# PiOBD_CM4_USB3.net
KiCad netlist of a schematic drawn in Altium Designer
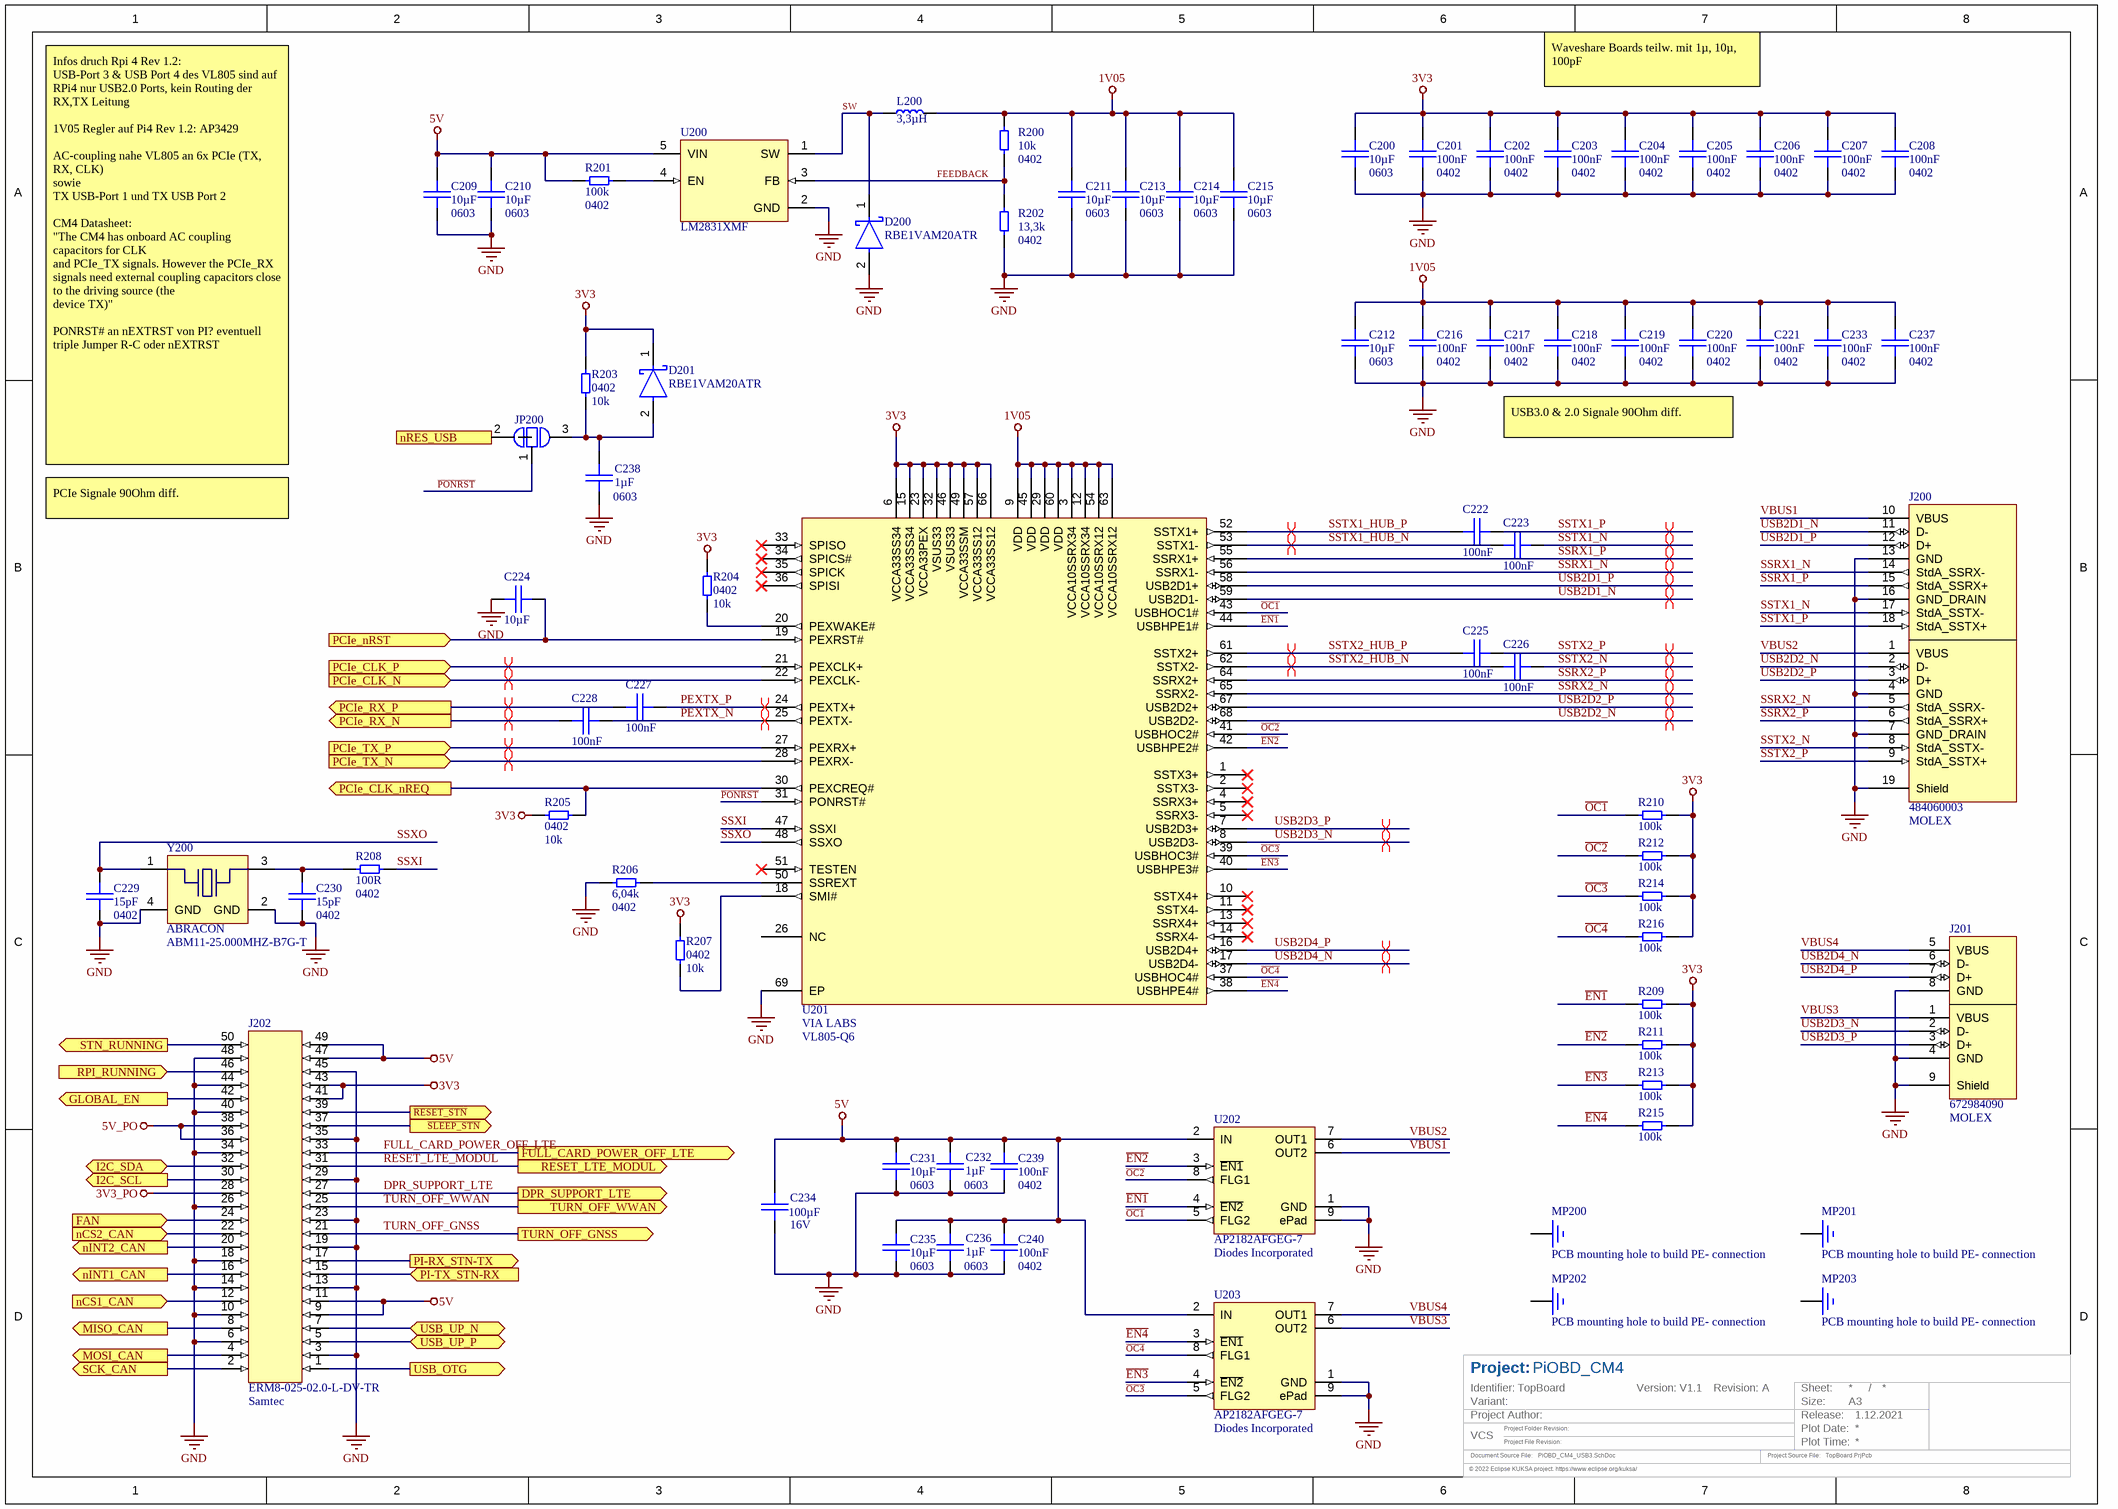
[diagram p0: PiOBD_CM4_USB3.SchDoc]

(export (version "E")
  (design (tool "Eeschema 10.0.6"))
  (components
    (comp (ref "C200")
      (value "CAP 0603 10µF -20% +20% 6.3V X5R")
      (footprint "CAP 0603 [1608 Metric] X080 N")
      (description "SMT 10µF ±20% 6,3 V Keramikkondensatoren X5R")
      (fields
        (field (name "MANUFACTURER PART NUMBER") "GRM188R60J106ME84")
        (field (name "CAPACITANCE") "10µF")
        (field (name "MANUFACTURER") "MURATA")
        (field (name "CASE") "0603")
      )
      (libsource (lib "ShareLib") (part "Capacitor non-polarized - Standard Schematic"))
    )
    (comp (ref "C201")
      (value "CAP 0402 100n -10% +10% 6.3V X7R")
      (footprint "CAP 0402 [1005 Metric] X050 N")
      (description "SMD/SMT 0402 6.3V -10% +10% X7R - Multilayer Ceramic Capacitors MLCC")
      (fields
        (field (name "MANUFACTURER") "MURATA")
        (field (name "CAPACITANCE") "100nF")
        (field (name "MANUFACTURER PART NUMBER") "GRM155R70J104KA01#")
        (field (name "CASE") "0402")
      )
      (libsource (lib "ShareLib") (part "Capacitor non-polarized - Standard Schematic"))
    )
    (comp (ref "C202")
      (value "CAP 0402 100n -10% +10% 6.3V X7R")
      (footprint "CAP 0402 [1005 Metric] X050 N")
      (description "SMD/SMT 0402 6.3V -10% +10% X7R - Multilayer Ceramic Capacitors MLCC")
      (fields
        (field (name "MANUFACTURER") "MURATA")
        (field (name "CAPACITANCE") "100nF")
        (field (name "MANUFACTURER PART NUMBER") "GRM155R70J104KA01#")
        (field (name "CASE") "0402")
      )
      (libsource (lib "ShareLib") (part "Capacitor non-polarized - Standard Schematic"))
    )
    (comp (ref "C203")
      (value "CAP 0402 100n -10% +10% 6.3V X7R")
      (footprint "CAP 0402 [1005 Metric] X050 N")
      (description "SMD/SMT 0402 6.3V -10% +10% X7R - Multilayer Ceramic Capacitors MLCC")
      (fields
        (field (name "MANUFACTURER") "MURATA")
        (field (name "CAPACITANCE") "100nF")
        (field (name "MANUFACTURER PART NUMBER") "GRM155R70J104KA01#")
        (field (name "CASE") "0402")
      )
      (libsource (lib "ShareLib") (part "Capacitor non-polarized - Standard Schematic"))
    )
    (comp (ref "C204")
      (value "CAP 0402 100n -10% +10% 6.3V X7R")
      (footprint "CAP 0402 [1005 Metric] X050 N")
      (description "SMD/SMT 0402 6.3V -10% +10% X7R - Multilayer Ceramic Capacitors MLCC")
      (fields
        (field (name "MANUFACTURER") "MURATA")
        (field (name "CAPACITANCE") "100nF")
        (field (name "MANUFACTURER PART NUMBER") "GRM155R70J104KA01#")
        (field (name "CASE") "0402")
      )
      (libsource (lib "ShareLib") (part "Capacitor non-polarized - Standard Schematic"))
    )
    (comp (ref "C205")
      (value "CAP 0402 100n -10% +10% 6.3V X7R")
      (footprint "CAP 0402 [1005 Metric] X050 N")
      (description "SMD/SMT 0402 6.3V -10% +10% X7R - Multilayer Ceramic Capacitors MLCC")
      (fields
        (field (name "MANUFACTURER") "MURATA")
        (field (name "CAPACITANCE") "100nF")
        (field (name "MANUFACTURER PART NUMBER") "GRM155R70J104KA01#")
        (field (name "CASE") "0402")
      )
      (libsource (lib "ShareLib") (part "Capacitor non-polarized - Standard Schematic"))
    )
    (comp (ref "C206")
      (value "CAP 0402 100n -10% +10% 6.3V X7R")
      (footprint "CAP 0402 [1005 Metric] X050 N")
      (description "SMD/SMT 0402 6.3V -10% +10% X7R - Multilayer Ceramic Capacitors MLCC")
      (fields
        (field (name "MANUFACTURER") "MURATA")
        (field (name "CAPACITANCE") "100nF")
        (field (name "MANUFACTURER PART NUMBER") "GRM155R70J104KA01#")
        (field (name "CASE") "0402")
      )
      (libsource (lib "ShareLib") (part "Capacitor non-polarized - Standard Schematic"))
    )
    (comp (ref "C207")
      (value "CAP 0402 100n -10% +10% 6.3V X7R")
      (footprint "CAP 0402 [1005 Metric] X050 N")
      (description "SMD/SMT 0402 6.3V -10% +10% X7R - Multilayer Ceramic Capacitors MLCC")
      (fields
        (field (name "MANUFACTURER") "MURATA")
        (field (name "CAPACITANCE") "100nF")
        (field (name "MANUFACTURER PART NUMBER") "GRM155R70J104KA01#")
        (field (name "CASE") "0402")
      )
      (libsource (lib "ShareLib") (part "Capacitor non-polarized - Standard Schematic"))
    )
    (comp (ref "C208")
      (value "CAP 0402 100n -10% +10% 6.3V X7R")
      (footprint "CAP 0402 [1005 Metric] X050 N")
      (description "SMD/SMT 0402 6.3V -10% +10% X7R - Multilayer Ceramic Capacitors MLCC")
      (fields
        (field (name "MANUFACTURER") "MURATA")
        (field (name "CAPACITANCE") "100nF")
        (field (name "MANUFACTURER PART NUMBER") "GRM155R70J104KA01#")
        (field (name "CASE") "0402")
      )
      (libsource (lib "ShareLib") (part "Capacitor non-polarized - Standard Schematic"))
    )
    (comp (ref "C209")
      (value "CAP 0603 10µF -20% +20% 6.3V X5R")
      (footprint "CAP 0603 [1608 Metric] X080 N")
      (description "SMT 10µF ±20% 6,3 V Keramikkondensatoren X5R")
      (fields
        (field (name "MANUFACTURER PART NUMBER") "GRM188R60J106ME84")
        (field (name "CAPACITANCE") "10µF")
        (field (name "MANUFACTURER") "MURATA")
        (field (name "CASE") "0603")
      )
      (libsource (lib "ShareLib") (part "Capacitor non-polarized - Standard Schematic"))
    )
    (comp (ref "C210")
      (value "CAP 0603 10µF -20% +20% 6.3V X5R")
      (footprint "CAP 0603 [1608 Metric] X080 N")
      (description "SMT 10µF ±20% 6,3 V Keramikkondensatoren X5R")
      (fields
        (field (name "MANUFACTURER PART NUMBER") "GRM188R60J106ME84")
        (field (name "CAPACITANCE") "10µF")
        (field (name "MANUFACTURER") "MURATA")
        (field (name "CASE") "0603")
      )
      (libsource (lib "ShareLib") (part "Capacitor non-polarized - Standard Schematic"))
    )
    (comp (ref "C211")
      (value "CAP 0603 10µF -20% +20% 6.3V X5R")
      (footprint "CAP 0603 [1608 Metric] X080 N")
      (description "SMT 10µF ±20% 6,3 V Keramikkondensatoren X5R")
      (fields
        (field (name "MANUFACTURER PART NUMBER") "GRM188R60J106ME84")
        (field (name "CAPACITANCE") "10µF")
        (field (name "MANUFACTURER") "MURATA")
        (field (name "CASE") "0603")
      )
      (libsource (lib "ShareLib") (part "Capacitor non-polarized - Standard Schematic"))
    )
    (comp (ref "C212")
      (value "CAP 0603 10µF -20% +20% 6.3V X5R")
      (footprint "CAP 0603 [1608 Metric] X080 N")
      (description "SMT 10µF ±20% 6,3 V Keramikkondensatoren X5R")
      (fields
        (field (name "MANUFACTURER PART NUMBER") "GRM188R60J106ME84")
        (field (name "CAPACITANCE") "10µF")
        (field (name "MANUFACTURER") "MURATA")
        (field (name "CASE") "0603")
      )
      (libsource (lib "ShareLib") (part "Capacitor non-polarized - Standard Schematic"))
    )
    (comp (ref "C213")
      (value "CAP 0603 10µF -20% +20% 6.3V X5R")
      (footprint "CAP 0603 [1608 Metric] X080 N")
      (description "SMT 10µF ±20% 6,3 V Keramikkondensatoren X5R")
      (fields
        (field (name "MANUFACTURER PART NUMBER") "GRM188R60J106ME84")
        (field (name "CAPACITANCE") "10µF")
        (field (name "MANUFACTURER") "MURATA")
        (field (name "CASE") "0603")
      )
      (libsource (lib "ShareLib") (part "Capacitor non-polarized - Standard Schematic"))
    )
    (comp (ref "C214")
      (value "CAP 0603 10µF -20% +20% 6.3V X5R")
      (footprint "CAP 0603 [1608 Metric] X080 N")
      (description "SMT 10µF ±20% 6,3 V Keramikkondensatoren X5R")
      (fields
        (field (name "MANUFACTURER PART NUMBER") "GRM188R60J106ME84")
        (field (name "CAPACITANCE") "10µF")
        (field (name "MANUFACTURER") "MURATA")
        (field (name "CASE") "0603")
      )
      (libsource (lib "ShareLib") (part "Capacitor non-polarized - Standard Schematic"))
    )
    (comp (ref "C215")
      (value "CAP 0603 10µF -20% +20% 6.3V X5R")
      (footprint "CAP 0603 [1608 Metric] X080 N")
      (description "SMT 10µF ±20% 6,3 V Keramikkondensatoren X5R")
      (fields
        (field (name "MANUFACTURER PART NUMBER") "GRM188R60J106ME84")
        (field (name "CAPACITANCE") "10µF")
        (field (name "MANUFACTURER") "MURATA")
        (field (name "CASE") "0603")
      )
      (libsource (lib "ShareLib") (part "Capacitor non-polarized - Standard Schematic"))
    )
    (comp (ref "C216")
      (value "CAP 0402 100n -10% +10% 6.3V X7R")
      (footprint "CAP 0402 [1005 Metric] X050 N")
      (description "SMD/SMT 0402 6.3V -10% +10% X7R - Multilayer Ceramic Capacitors MLCC")
      (fields
        (field (name "MANUFACTURER") "MURATA")
        (field (name "CAPACITANCE") "100nF")
        (field (name "MANUFACTURER PART NUMBER") "GRM155R70J104KA01#")
        (field (name "CASE") "0402")
      )
      (libsource (lib "ShareLib") (part "Capacitor non-polarized - Standard Schematic"))
    )
    (comp (ref "C217")
      (value "CAP 0402 100n -10% +10% 6.3V X7R")
      (footprint "CAP 0402 [1005 Metric] X050 N")
      (description "SMD/SMT 0402 6.3V -10% +10% X7R - Multilayer Ceramic Capacitors MLCC")
      (fields
        (field (name "MANUFACTURER") "MURATA")
        (field (name "CAPACITANCE") "100nF")
        (field (name "MANUFACTURER PART NUMBER") "GRM155R70J104KA01#")
        (field (name "CASE") "0402")
      )
      (libsource (lib "ShareLib") (part "Capacitor non-polarized - Standard Schematic"))
    )
    (comp (ref "C218")
      (value "CAP 0402 100n -10% +10% 6.3V X7R")
      (footprint "CAP 0402 [1005 Metric] X050 N")
      (description "SMD/SMT 0402 6.3V -10% +10% X7R - Multilayer Ceramic Capacitors MLCC")
      (fields
        (field (name "MANUFACTURER") "MURATA")
        (field (name "CAPACITANCE") "100nF")
        (field (name "MANUFACTURER PART NUMBER") "GRM155R70J104KA01#")
        (field (name "CASE") "0402")
      )
      (libsource (lib "ShareLib") (part "Capacitor non-polarized - Standard Schematic"))
    )
    (comp (ref "C219")
      (value "CAP 0402 100n -10% +10% 6.3V X7R")
      (footprint "CAP 0402 [1005 Metric] X050 N")
      (description "SMD/SMT 0402 6.3V -10% +10% X7R - Multilayer Ceramic Capacitors MLCC")
      (fields
        (field (name "MANUFACTURER") "MURATA")
        (field (name "CAPACITANCE") "100nF")
        (field (name "MANUFACTURER PART NUMBER") "GRM155R70J104KA01#")
        (field (name "CASE") "0402")
      )
      (libsource (lib "ShareLib") (part "Capacitor non-polarized - Standard Schematic"))
    )
    (comp (ref "C220")
      (value "CAP 0402 100n -10% +10% 6.3V X7R")
      (footprint "CAP 0402 [1005 Metric] X050 N")
      (description "SMD/SMT 0402 6.3V -10% +10% X7R - Multilayer Ceramic Capacitors MLCC")
      (fields
        (field (name "MANUFACTURER") "MURATA")
        (field (name "CAPACITANCE") "100nF")
        (field (name "MANUFACTURER PART NUMBER") "GRM155R70J104KA01#")
        (field (name "CASE") "0402")
      )
      (libsource (lib "ShareLib") (part "Capacitor non-polarized - Standard Schematic"))
    )
    (comp (ref "C221")
      (value "CAP 0402 100n -10% +10% 6.3V X7R")
      (footprint "CAP 0402 [1005 Metric] X050 N")
      (description "SMD/SMT 0402 6.3V -10% +10% X7R - Multilayer Ceramic Capacitors MLCC")
      (fields
        (field (name "MANUFACTURER") "MURATA")
        (field (name "CAPACITANCE") "100nF")
        (field (name "MANUFACTURER PART NUMBER") "GRM155R70J104KA01#")
        (field (name "CASE") "0402")
      )
      (libsource (lib "ShareLib") (part "Capacitor non-polarized - Standard Schematic"))
    )
    (comp (ref "C222")
      (value "CAP 0402 100n -10% +10% 6.3V X7R")
      (footprint "CAP 0402 [1005 Metric] X050 N")
      (description "SMD/SMT 0402 6.3V -10% +10% X7R - Multilayer Ceramic Capacitors MLCC")
      (fields
        (field (name "MANUFACTURER") "MURATA")
        (field (name "CAPACITANCE") "100nF")
        (field (name "MANUFACTURER PART NUMBER") "GRM155R70J104KA01#")
      )
      (libsource (lib "ShareLib") (part "Capacitor non-polarized - Standard Schematic"))
    )
    (comp (ref "C223")
      (value "CAP 0402 100n -10% +10% 6.3V X7R")
      (footprint "CAP 0402 [1005 Metric] X050 N")
      (description "SMD/SMT 0402 6.3V -10% +10% X7R - Multilayer Ceramic Capacitors MLCC")
      (fields
        (field (name "MANUFACTURER") "MURATA")
        (field (name "CAPACITANCE") "100nF")
        (field (name "MANUFACTURER PART NUMBER") "GRM155R70J104KA01#")
      )
      (libsource (lib "ShareLib") (part "Capacitor non-polarized - Standard Schematic"))
    )
    (comp (ref "C224")
      (value "CAP 0603 10µF -20% +20% 6.3V X5R")
      (footprint "CAP 0603 [1608 Metric] X080 N")
      (description "SMT 10µF ±20% 6,3 V Keramikkondensatoren X5R")
      (fields
        (field (name "MANUFACTURER PART NUMBER") "GRM188R60J106ME84")
        (field (name "CAPACITANCE") "10µF")
        (field (name "MANUFACTURER") "MURATA")
      )
      (libsource (lib "ShareLib") (part "Capacitor non-polarized - Standard Schematic"))
    )
    (comp (ref "C225")
      (value "CAP 0402 100n -10% +10% 6.3V X7R")
      (footprint "CAP 0402 [1005 Metric] X050 N")
      (description "SMD/SMT 0402 6.3V -10% +10% X7R - Multilayer Ceramic Capacitors MLCC")
      (fields
        (field (name "MANUFACTURER") "MURATA")
        (field (name "CAPACITANCE") "100nF")
        (field (name "MANUFACTURER PART NUMBER") "GRM155R70J104KA01#")
      )
      (libsource (lib "ShareLib") (part "Capacitor non-polarized - Standard Schematic"))
    )
    (comp (ref "C226")
      (value "CAP 0402 100n -10% +10% 6.3V X7R")
      (footprint "CAP 0402 [1005 Metric] X050 N")
      (description "SMD/SMT 0402 6.3V -10% +10% X7R - Multilayer Ceramic Capacitors MLCC")
      (fields
        (field (name "MANUFACTURER") "MURATA")
        (field (name "CAPACITANCE") "100nF")
        (field (name "MANUFACTURER PART NUMBER") "GRM155R70J104KA01#")
      )
      (libsource (lib "ShareLib") (part "Capacitor non-polarized - Standard Schematic"))
    )
    (comp (ref "C227")
      (value "CAP 0402 100n -10% +10% 6.3V X7R")
      (footprint "CAP 0402 [1005 Metric] X050 N")
      (description "SMD/SMT 0402 6.3V -10% +10% X7R - Multilayer Ceramic Capacitors MLCC")
      (fields
        (field (name "MANUFACTURER") "MURATA")
        (field (name "CAPACITANCE") "100nF")
        (field (name "MANUFACTURER PART NUMBER") "GRM155R70J104KA01#")
      )
      (libsource (lib "ShareLib") (part "Capacitor non-polarized - Standard Schematic"))
    )
    (comp (ref "C228")
      (value "CAP 0402 100n -10% +10% 6.3V X7R")
      (footprint "CAP 0402 [1005 Metric] X050 N")
      (description "SMD/SMT 0402 6.3V -10% +10% X7R - Multilayer Ceramic Capacitors MLCC")
      (fields
        (field (name "MANUFACTURER") "MURATA")
        (field (name "CAPACITANCE") "100nF")
        (field (name "MANUFACTURER PART NUMBER") "GRM155R70J104KA01#")
      )
      (libsource (lib "ShareLib") (part "Capacitor non-polarized - Standard Schematic"))
    )
    (comp (ref "C229")
      (value "CAP 0402 15p -2% +2% 25V C0G")
      (footprint "CAP 0402 [1005 Metric] X050 N")
      (description "SMD/SMT 0402 25V -2% +2% C0G - Multilayer Ceramic Capacitors MLCC")
      (fields
        (field (name "MANUFACTURER") "MURATA")
        (field (name "MANUFACTURER PART NUMBER") "GRM1555C1E150GA01#")
        (field (name "CASE") "0402")
        (field (name "CAPACITANCE") "15pF")
      )
      (libsource (lib "ShareLib") (part "Capacitor non-polarized - Standard Schematic"))
    )
    (comp (ref "C230")
      (value "CAP 0402 15p -2% +2% 25V C0G")
      (footprint "CAP 0402 [1005 Metric] X050 N")
      (description "SMD/SMT 0402 25V -2% +2% C0G - Multilayer Ceramic Capacitors MLCC")
      (fields
        (field (name "MANUFACTURER") "MURATA")
        (field (name "MANUFACTURER PART NUMBER") "GRM1555C1E150GA01#")
        (field (name "CASE") "0402")
        (field (name "CAPACITANCE") "15pF")
      )
      (libsource (lib "ShareLib") (part "Capacitor non-polarized - Standard Schematic"))
    )
    (comp (ref "C231")
      (value "CAP 0603 10µF -20% +20% 6.3V X5R")
      (footprint "CAP 0603 [1608 Metric] X080 N")
      (description "SMT 10µF ±20% 6,3 V Keramikkondensatoren X5R")
      (fields
        (field (name "MANUFACTURER PART NUMBER") "GRM188R60J106ME84")
        (field (name "CAPACITANCE") "10µF")
        (field (name "MANUFACTURER") "MURATA")
        (field (name "CASE") "0603")
      )
      (libsource (lib "ShareLib") (part "Capacitor non-polarized - Standard Schematic"))
    )
    (comp (ref "C232")
      (value "CAP 0603 1u -10% +10% 10V X7R")
      (footprint "CAP 0603 [1608 Metric] X080 N")
      (description "SMD/SMT 0603 10V -10% +10% X7R - Multilayer Ceramic Capacitors MLCC")
      (fields
        (field (name "CAPACITANCE") "1µF")
        (field (name "MANUFACTURER PART NUMBER") "GRM188R71A105KA61#")
        (field (name "MANUFACTURER") "MURATA")
        (field (name "CASE") "0603")
      )
      (libsource (lib "ShareLib") (part "Capacitor non-polarized - Standard Schematic"))
    )
    (comp (ref "C233")
      (value "CAP 0402 100n -10% +10% 6.3V X7R")
      (footprint "CAP 0402 [1005 Metric] X050 N")
      (description "SMD/SMT 0402 6.3V -10% +10% X7R - Multilayer Ceramic Capacitors MLCC")
      (fields
        (field (name "MANUFACTURER") "MURATA")
        (field (name "CAPACITANCE") "100nF")
        (field (name "MANUFACTURER PART NUMBER") "GRM155R70J104KA01#")
        (field (name "CASE") "0402")
      )
      (libsource (lib "ShareLib") (part "Capacitor non-polarized - Standard Schematic"))
    )
    (comp (ref "C234")
      (value "CAP 1210 100µF +/-20% 16V X5R")
      (footprint "CAP 1210 [3225 Metric] X250 N")
      (description "100µF ±20% 16V Ceramic Capacitor X5R 1210 (3225 Metric)")
      (fields
        (field (name "MANUFACTURER PART NUMBER") "EMK325ABJ107MM-T")
        (field (name "VOLTAGE RATING") "16V")
        (field (name "MANUFACTURER") "TAIYO YUDEN")
        (field (name "CAPACITANCE") "100µF")
      )
      (libsource (lib "ShareLib") (part "Capacitor non-polarized - Standard Schematic"))
    )
    (comp (ref "C235")
      (value "CAP 0603 10µF -20% +20% 6.3V X5R")
      (footprint "CAP 0603 [1608 Metric] X080 N")
      (description "SMT 10µF ±20% 6,3 V Keramikkondensatoren X5R")
      (fields
        (field (name "MANUFACTURER PART NUMBER") "GRM188R60J106ME84")
        (field (name "CAPACITANCE") "10µF")
        (field (name "MANUFACTURER") "MURATA")
        (field (name "CASE") "0603")
      )
      (libsource (lib "ShareLib") (part "Capacitor non-polarized - Standard Schematic"))
    )
    (comp (ref "C236")
      (value "CAP 0603 1u -10% +10% 10V X7R")
      (footprint "CAP 0603 [1608 Metric] X080 N")
      (description "SMD/SMT 0603 10V -10% +10% X7R - Multilayer Ceramic Capacitors MLCC")
      (fields
        (field (name "CAPACITANCE") "1µF")
        (field (name "MANUFACTURER PART NUMBER") "GRM188R71A105KA61#")
        (field (name "MANUFACTURER") "MURATA")
        (field (name "CASE") "0603")
      )
      (libsource (lib "ShareLib") (part "Capacitor non-polarized - Standard Schematic"))
    )
    (comp (ref "C237")
      (value "CAP 0402 100n -10% +10% 6.3V X7R")
      (footprint "CAP 0402 [1005 Metric] X050 N")
      (description "SMD/SMT 0402 6.3V -10% +10% X7R - Multilayer Ceramic Capacitors MLCC")
      (fields
        (field (name "MANUFACTURER") "MURATA")
        (field (name "CAPACITANCE") "100nF")
        (field (name "MANUFACTURER PART NUMBER") "GRM155R70J104KA01#")
        (field (name "CASE") "0402")
      )
      (libsource (lib "ShareLib") (part "Capacitor non-polarized - Standard Schematic"))
    )
    (comp (ref "C238")
      (value "CAP 0603 1u -10% +10% 10V X7R")
      (footprint "CAP 0603 [1608 Metric] X080 N")
      (description "SMD/SMT 0603 10V -10% +10% X7R - Multilayer Ceramic Capacitors MLCC")
      (fields
        (field (name "CAPACITANCE") "1µF")
        (field (name "MANUFACTURER PART NUMBER") "GRM188R71A105KA61#")
        (field (name "MANUFACTURER") "MURATA")
        (field (name "CASE") "0603")
      )
      (libsource (lib "ShareLib") (part "Capacitor non-polarized - Standard Schematic"))
    )
    (comp (ref "C239")
      (value "CAP 0402 100n -10% +10% 6.3V X7R")
      (footprint "CAP 0402 [1005 Metric] X050 N")
      (description "SMD/SMT 0402 6.3V -10% +10% X7R - Multilayer Ceramic Capacitors MLCC")
      (fields
        (field (name "MANUFACTURER") "MURATA")
        (field (name "CAPACITANCE") "100nF")
        (field (name "MANUFACTURER PART NUMBER") "GRM155R70J104KA01#")
        (field (name "CASE") "0402")
      )
      (libsource (lib "ShareLib") (part "Capacitor non-polarized - Standard Schematic"))
    )
    (comp (ref "C240")
      (value "CAP 0402 100n -10% +10% 6.3V X7R")
      (footprint "CAP 0402 [1005 Metric] X050 N")
      (description "SMD/SMT 0402 6.3V -10% +10% X7R - Multilayer Ceramic Capacitors MLCC")
      (fields
        (field (name "MANUFACTURER") "MURATA")
        (field (name "CAPACITANCE") "100nF")
        (field (name "MANUFACTURER PART NUMBER") "GRM155R70J104KA01#")
        (field (name "CASE") "0402")
      )
      (libsource (lib "ShareLib") (part "Capacitor non-polarized - Standard Schematic"))
    )
    (comp (ref "D200")
      (value "RBE1VAM20ATR")
      (footprint "FP-TUMD2M-MFG")
      (description "DIODE SCHOTTKY 20V 1A TUMD2M")
      (fields
        (field (name "OCTOPART") "https://octopart.com/rbe1vam20atr-rohm-50418626")
        (field (name "MANUFACTURER") "Rohm")
      )
      (libsource (lib "Altium Content Vault") (part "c1678fac7984e62e0809fbf79c06691"))
    )
    (comp (ref "D201")
      (value "RBE1VAM20ATR")
      (footprint "FP-TUMD2M-MFG")
      (description "DIODE SCHOTTKY 20V 1A TUMD2M")
      (fields
        (field (name "OCTOPART") "https://octopart.com/rbe1vam20atr-rohm-50418626")
        (field (name "MANUFACTURER") "Rohm")
      )
      (libsource (lib "Altium Content Vault") (part "c1678fac7984e62e0809fbf79c06691"))
    )
    (comp (ref "J200")
      (value "MOLEX - 484060003")
      (footprint "MOLEX - 484060003")
      (fields (field (name "MANUFACTURER PART NUMBER") "484060003") (field (name "MANUFACTURER") "MOLEX"))
      (libsource (lib "ShareLib") (part "MOLEX - 484060003"))
    )
    (comp (ref "J201")
      (value "MOLEX - 672984090")
      (footprint "MOLEX - 672984090")
      (fields (field (name "MANUFACTURER PART NUMBER") "672984090") (field (name "MANUFACTURER") "MOLEX"))
      (libsource (lib "ShareLib") (part "MOLEX - 672984090"))
    )
    (comp (ref "J202")
      (value "SAMTEC - ERM8-025-02.0-L-DV-TR")
      (footprint "SAMTEC - ERM8-025-02.0-S-DV-TR-Footprint-1")
      (description "50 Poliger Steckverbinder Steckleiste, Mittenstreifenkontakte Oberflächenmontage Gold")
      (fields
        (field (name "MANUFACTURER PART NUMBER") "ERM8-025-02.0-L-DV-TR")
        (field (name "MANUFACTURER") "Samtec")
      )
      (libsource (lib "ShareLib") (part "SAMTEC - ERM8-025-02.0-S-DV-TR"))
    )
    (comp (ref "JP200")
      (value "Solder Jumper Triple 0402 with Assembly between 1 and 2")
      (footprint "Solder Jumper Triple 0402 with Assembly between 1 and 2")
      (fields
        (field (name "MANUFACTURER") "YAGEO")
        (field (name "MANUFACTURER PART NUMBER") "RC0402JR-070RL")
      )
      (libsource (lib "ShareLib") (part "Solder Jumper tripple with Assembly between 1 and 2"))
    )
    (comp (ref "L200")
      (value "VISHAY - IFSC1515AHER3R3M01")
      (footprint "IFSC-1515AH")
      (description "Low Profile, High Current Inductor")
      (fields
        (field (name "MANUFACTURER PART NUMBER") "IFSC1515AHER3R3M01")
        (field (name "MANUFACTURER") "VISHAY")
        (field (name "INDUCTANCE") "3,3µH")
      )
      (libsource (lib "ShareLib") (part "Standard Schematic - Inductor Universal"))
    )
    (comp (ref "MP200")
      (value "PCB mounting hole to build PE- connection")
      (footprint "MountingPad")
      (description "PCB mounting hole to build PE- connection, hole diameter 4.3mm")
      (libsource (lib "ShareLib") (part "PCB mounting hole (no BOM)"))
    )
    (comp (ref "MP201")
      (value "PCB mounting hole to build PE- connection")
      (footprint "MountingPad")
      (description "PCB mounting hole to build PE- connection, hole diameter 4.3mm")
      (libsource (lib "ShareLib") (part "PCB mounting hole (no BOM)"))
    )
    (comp (ref "MP202")
      (value "PCB mounting hole to build PE- connection")
      (footprint "MountingPad")
      (description "PCB mounting hole to build PE- connection, hole diameter 4.3mm")
      (libsource (lib "ShareLib") (part "PCB mounting hole (no BOM)"))
    )
    (comp (ref "MP203")
      (value "PCB mounting hole to build PE- connection")
      (footprint "MountingPad")
      (description "PCB mounting hole to build PE- connection, hole diameter 4.3mm")
      (libsource (lib "ShareLib") (part "PCB mounting hole (no BOM)"))
    )
    (comp (ref "R200")
      (value "RES 0402 10K 1% 0W0625")
      (footprint "RES 0402 [1005 Metric]_N")
      (description "RC0402 series chip resistor with lead-free terminations made by thick film process")
      (fields
        (field (name "MANUFACTURER PART NUMBER") "RC0402FR-0710KL")
        (field (name "CASE") "0402")
        (field (name "MANUFACTURER") "YAGEO")
        (field (name "RESISTANCE") "10k")
      )
      (libsource (lib "ShareLib") (part "Standard Schematic - Resistor Universal"))
    )
    (comp (ref "R201")
      (value "RES 0402 100K 1% 0W0625")
      (footprint "RES 0402 [1005 Metric]_N")
      (description "RC0402 series chip resistor with lead-free terminations made by thick film process")
      (fields
        (field (name "RESISTANCE") "100k")
        (field (name "MANUFACTURER PART NUMBER") "RC0402FR-07100KL")
        (field (name "CASE") "0402")
        (field (name "MANUFACTURER") "YAGEO")
      )
      (libsource (lib "ShareLib") (part "Standard Schematic - Resistor Universal"))
    )
    (comp (ref "R202")
      (value "RES 0402 13K3 1% 0W0625")
      (footprint "RES 0402 [1005 Metric]_N")
      (description "RC0402 series chip resistor with lead-free terminations made by thick film process")
      (fields
        (field (name "MANUFACTURER") "YAGEO")
        (field (name "RESISTANCE") "13,3k")
        (field (name "CASE") "0402")
        (field (name "MANUFACTURER PART NUMBER") "RC0402FR-0713K3L")
      )
      (libsource (lib "ShareLib") (part "Standard Schematic - Resistor Universal"))
    )
    (comp (ref "R203")
      (value "RES 0402 10K 1% 0W0625")
      (footprint "RES 0402 [1005 Metric]_N")
      (description "RC0402 series chip resistor with lead-free terminations made by thick film process")
      (fields
        (field (name "MANUFACTURER PART NUMBER") "RC0402FR-0710KL")
        (field (name "CASE") "0402")
        (field (name "MANUFACTURER") "YAGEO")
        (field (name "RESISTANCE") "10k")
      )
      (libsource (lib "ShareLib") (part "Standard Schematic - Resistor Universal"))
    )
    (comp (ref "R204")
      (value "RES 0402 10K 1% 0W0625")
      (footprint "RES 0402 [1005 Metric]_N")
      (description "RC0402 series chip resistor with lead-free terminations made by thick film process")
      (fields
        (field (name "MANUFACTURER PART NUMBER") "RC0402FR-0710KL")
        (field (name "CASE") "0402")
        (field (name "MANUFACTURER") "YAGEO")
        (field (name "RESISTANCE") "10k")
      )
      (libsource (lib "ShareLib") (part "Standard Schematic - Resistor Universal"))
    )
    (comp (ref "R205")
      (value "RES 0402 10K 1% 0W0625")
      (footprint "RES 0402 [1005 Metric]_N")
      (description "RC0402 series chip resistor with lead-free terminations made by thick film process")
      (fields
        (field (name "MANUFACTURER PART NUMBER") "RC0402FR-0710KL")
        (field (name "CASE") "0402")
        (field (name "MANUFACTURER") "YAGEO")
        (field (name "RESISTANCE") "10k")
      )
      (libsource (lib "ShareLib") (part "Standard Schematic - Resistor Universal"))
    )
    (comp (ref "R206")
      (value "RES 0402 6K04 1% 0W0625")
      (footprint "RES 0402 [1005 Metric]_N")
      (description "RC0402 series chip resistor with lead-free terminations made by thick film process")
      (fields
        (field (name "RESISTANCE") "6,04k")
        (field (name "MANUFACTURER") "YAGEO")
        (field (name "MANUFACTURER PART NUMBER") "RC0402FR-076K04L")
        (field (name "CASE") "0402")
      )
      (libsource (lib "ShareLib") (part "Standard Schematic - Resistor Universal"))
    )
    (comp (ref "R207")
      (value "RES 0402 10K 1% 0W0625")
      (footprint "RES 0402 [1005 Metric]_N")
      (description "RC0402 series chip resistor with lead-free terminations made by thick film process")
      (fields
        (field (name "MANUFACTURER PART NUMBER") "RC0402FR-0710KL")
        (field (name "CASE") "0402")
        (field (name "MANUFACTURER") "YAGEO")
        (field (name "RESISTANCE") "10k")
      )
      (libsource (lib "ShareLib") (part "Standard Schematic - Resistor Universal"))
    )
    (comp (ref "R208")
      (value "RES 0402 100R 1% 63mW")
      (footprint "RES 0402 [1005 Metric]_N")
      (description "RC0402 series chip resistor with lead-free terminations made by thick film process")
      (fields
        (field (name "RESISTANCE") "100R")
        (field (name "CASE") "0402")
        (field (name "MANUFACTURER") "ROHM")
        (field (name "MANUFACTURER PART NUMBER") "MCR01MZPF100")
      )
      (libsource (lib "ShareLib") (part "Standard Schematic - Resistor Universal"))
    )
    (comp (ref "R209")
      (value "RES 0402 100K 1% 0W0625")
      (footprint "RES 0402 [1005 Metric]_N")
      (description "RC0402 series chip resistor with lead-free terminations made by thick film process")
      (fields
        (field (name "RESISTANCE") "100k")
        (field (name "MANUFACTURER PART NUMBER") "RC0402FR-07100KL")
        (field (name "MANUFACTURER") "YAGEO")
      )
      (libsource (lib "ShareLib") (part "Standard Schematic - Resistor Universal"))
    )
    (comp (ref "R210")
      (value "RES 0402 100K 1% 0W0625")
      (footprint "RES 0402 [1005 Metric]_N")
      (description "RC0402 series chip resistor with lead-free terminations made by thick film process")
      (fields
        (field (name "RESISTANCE") "100k")
        (field (name "MANUFACTURER PART NUMBER") "RC0402FR-07100KL")
        (field (name "MANUFACTURER") "YAGEO")
      )
      (libsource (lib "ShareLib") (part "Standard Schematic - Resistor Universal"))
    )
    (comp (ref "R211")
      (value "RES 0402 100K 1% 0W0625")
      (footprint "RES 0402 [1005 Metric]_N")
      (description "RC0402 series chip resistor with lead-free terminations made by thick film process")
      (fields
        (field (name "RESISTANCE") "100k")
        (field (name "MANUFACTURER PART NUMBER") "RC0402FR-07100KL")
        (field (name "MANUFACTURER") "YAGEO")
      )
      (libsource (lib "ShareLib") (part "Standard Schematic - Resistor Universal"))
    )
    (comp (ref "R212")
      (value "RES 0402 100K 1% 0W0625")
      (footprint "RES 0402 [1005 Metric]_N")
      (description "RC0402 series chip resistor with lead-free terminations made by thick film process")
      (fields
        (field (name "RESISTANCE") "100k")
        (field (name "MANUFACTURER PART NUMBER") "RC0402FR-07100KL")
        (field (name "MANUFACTURER") "YAGEO")
      )
      (libsource (lib "ShareLib") (part "Standard Schematic - Resistor Universal"))
    )
    (comp (ref "R213")
      (value "RES 0402 100K 1% 0W0625")
      (footprint "RES 0402 [1005 Metric]_N")
      (description "RC0402 series chip resistor with lead-free terminations made by thick film process")
      (fields
        (field (name "RESISTANCE") "100k")
        (field (name "MANUFACTURER PART NUMBER") "RC0402FR-07100KL")
        (field (name "MANUFACTURER") "YAGEO")
      )
      (libsource (lib "ShareLib") (part "Standard Schematic - Resistor Universal"))
    )
    (comp (ref "R214")
      (value "RES 0402 100K 1% 0W0625")
      (footprint "RES 0402 [1005 Metric]_N")
      (description "RC0402 series chip resistor with lead-free terminations made by thick film process")
      (fields
        (field (name "RESISTANCE") "100k")
        (field (name "MANUFACTURER PART NUMBER") "RC0402FR-07100KL")
        (field (name "MANUFACTURER") "YAGEO")
      )
      (libsource (lib "ShareLib") (part "Standard Schematic - Resistor Universal"))
    )
    (comp (ref "R215")
      (value "RES 0402 100K 1% 0W0625")
      (footprint "RES 0402 [1005 Metric]_N")
      (description "RC0402 series chip resistor with lead-free terminations made by thick film process")
      (fields
        (field (name "RESISTANCE") "100k")
        (field (name "MANUFACTURER PART NUMBER") "RC0402FR-07100KL")
        (field (name "MANUFACTURER") "YAGEO")
      )
      (libsource (lib "ShareLib") (part "Standard Schematic - Resistor Universal"))
    )
    (comp (ref "R216")
      (value "RES 0402 100K 1% 0W0625")
      (footprint "RES 0402 [1005 Metric]_N")
      (description "RC0402 series chip resistor with lead-free terminations made by thick film process")
      (fields
        (field (name "RESISTANCE") "100k")
        (field (name "MANUFACTURER PART NUMBER") "RC0402FR-07100KL")
        (field (name "MANUFACTURER") "YAGEO")
      )
      (libsource (lib "ShareLib") (part "Standard Schematic - Resistor Universal"))
    )
    (comp (ref "U200")
      (value "LM2831XMF")
      (footprint "MF05A_N")
      (description "High Frequency 1.5A Load - Step-Down DC-DC Regulator, 5-pin SOT-23")
      (fields (field (name "MANUFACTURER") "National Semiconductor"))
      (libsource (lib "Altium Content Vault") (part "PM-DCDC-LM2830XMF"))
    )
    (comp (ref "U201")
      (value "VIA LABS - VL805")
      (footprint "QFN40P800X800X90_HS-69N")
      (description "VL805 4-Port USB 3.0 Host Controller")
      (fields (field (name "MANUFACTURER") "VIA LABS") (field (name "MANUFACTURER PART NUMBER") "VL805-Q6"))
      (libsource (lib "ShareLib") (part "VIA LABS - VL805"))
    )
    (comp (ref "U202")
      (value "DIODES INCORPORATED - AP2182A")
      (footprint "SON65P300X60_HS-9N")
      (description "Power Switch/Driver 1:2 P-Channel 1.5A U-DFN3030-8 (Type E)")
      (fields
        (field (name "MANUFACTURER PART NUMBER") "AP2182AFGEG-7")
        (field (name "MANUFACTURER") "Diodes Incorporated")
      )
      (libsource (lib "ShareLib") (part "DIODES INCORPORATED - AP2182A"))
    )
    (comp (ref "U203")
      (value "DIODES INCORPORATED - AP2182A")
      (footprint "SON65P300X60_HS-9N")
      (description "Power Switch/Driver 1:2 P-Channel 1.5A U-DFN3030-8 (Type E)")
      (fields
        (field (name "MANUFACTURER PART NUMBER") "AP2182AFGEG-7")
        (field (name "MANUFACTURER") "Diodes Incorporated")
      )
      (libsource (lib "ShareLib") (part "DIODES INCORPORATED - AP2182A"))
    )
    (comp (ref "Y200")
      (value "ABRACON - ABM11-25.000MHZ-B7G-T")
      (footprint "ABM11")
      (description "25.000MHz ±15ppm Crystal 10pF 100 Ohm -20°C +70°C Surface Mount 4-SMD, No Lead (DFN, LCC)")
      (fields
        (field (name "MANUFACTURER") "ABRACON")
        (field (name "MANUFACTURER PART NUMBER") "ABM11-25.000MHZ-B7G-T")
      )
      (libsource (lib "ShareLib") (part "Crystal 4-Pin, 1+3-Feed / 2+4-GND"))
    )
  )
  (nets
    (net (code "1") (name "/DPR_SUPPORT_LTE") (class "Default")
      (node (ref "J202") (pin "27") (pintype "input"))
    )
    (net (code "2") (name "/EN1") (class "Default")
      (node (ref "R209") (pin "2") (pinfunction "2_2") (pintype "passive"))
      (node (ref "U201") (pin "44") (pinfunction "USBHPE1#_44") (pintype "output"))
      (node (ref "U202") (pin "4") (pinfunction "EN2_4") (pintype "input"))
    )
    (net (code "3") (name "/EN2") (class "Default")
      (node (ref "R211") (pin "2") (pinfunction "2_2") (pintype "passive"))
      (node (ref "U201") (pin "42") (pinfunction "USBHPE2#_42") (pintype "output"))
      (node (ref "U202") (pin "3") (pinfunction "EN1_3") (pintype "input"))
    )
    (net (code "4") (name "/EN3") (class "Default")
      (node (ref "R213") (pin "2") (pinfunction "2_2") (pintype "passive"))
      (node (ref "U201") (pin "40") (pinfunction "USBHPE3#_40") (pintype "output"))
      (node (ref "U203") (pin "4") (pinfunction "EN2_4") (pintype "input"))
    )
    (net (code "5") (name "/EN4") (class "Default")
      (node (ref "R215") (pin "2") (pinfunction "2_2") (pintype "passive"))
      (node (ref "U201") (pin "38") (pinfunction "USBHPE4#_38") (pintype "output"))
      (node (ref "U203") (pin "3") (pinfunction "EN1_3") (pintype "input"))
    )
    (net (code "6") (name "/FAN") (class "Default") (node (ref "J202") (pin "24") (pintype "input")))
    (net (code "7") (name "/FEEDBACK") (class "Default")
      (node (ref "R200") (pin "2") (pinfunction "2_2") (pintype "passive"))
      (node (ref "R202") (pin "2") (pinfunction "2_2") (pintype "passive"))
      (node (ref "U200") (pin "3") (pinfunction "FB_3") (pintype "input"))
    )
    (net (code "8") (name "/FULL_CARD_POWER_OFF_LTE") (class "Default")
      (node (ref "J202") (pin "33") (pintype "input"))
    )
    (net (code "9") (name "/GLOBAL_EN") (class "Default") (node (ref "J202") (pin "42") (pintype "input")))
    (net (code "10") (name "/I2C_SCL") (class "Default") (node (ref "J202") (pin "30") (pintype "input")))
    (net (code "11") (name "/I2C_SDA") (class "Default") (node (ref "J202") (pin "32") (pintype "input")))
    (net (code "12") (name "/MISO_CAN") (class "Default") (node (ref "J202") (pin "8") (pintype "input")))
    (net (code "13") (name "/MOSI_CAN") (class "Default") (node (ref "J202") (pin "4") (pintype "input")))
    (net (code "14") (name "/OC1") (class "Default")
      (node (ref "R210") (pin "2") (pinfunction "2_2") (pintype "passive"))
      (node (ref "U201") (pin "43") (pinfunction "USBHOC1#_43") (pintype "input"))
      (node (ref "U202") (pin "5") (pinfunction "FLG2_5") (pintype "output"))
    )
    (net (code "15") (name "/OC2") (class "Default")
      (node (ref "R212") (pin "2") (pinfunction "2_2") (pintype "passive"))
      (node (ref "U201") (pin "41") (pinfunction "USBHOC2#_41") (pintype "input"))
      (node (ref "U202") (pin "8") (pinfunction "FLG1_8") (pintype "output"))
    )
    (net (code "16") (name "/OC3") (class "Default")
      (node (ref "R214") (pin "2") (pinfunction "2_2") (pintype "passive"))
      (node (ref "U201") (pin "39") (pinfunction "USBHOC3#_39") (pintype "input"))
      (node (ref "U203") (pin "5") (pinfunction "FLG2_5") (pintype "output"))
    )
    (net (code "17") (name "/OC4") (class "Default")
      (node (ref "R216") (pin "2") (pinfunction "2_2") (pintype "passive"))
      (node (ref "U201") (pin "37") (pinfunction "USBHOC4#_37") (pintype "input"))
      (node (ref "U203") (pin "8") (pinfunction "FLG1_8") (pintype "output"))
    )
    (net (code "18") (name "/PCIe_CLK_N") (class "Default")
      (node (ref "U201") (pin "22") (pinfunction "PEXCLK-_22") (pintype "input"))
    )
    (net (code "19") (name "/PCIe_CLK_P") (class "Default")
      (node (ref "U201") (pin "21") (pinfunction "PEXCLK+_21") (pintype "input"))
    )
    (net (code "20") (name "/PCIe_CLK_nREQ") (class "Default")
      (node (ref "R205") (pin "2") (pinfunction "2_2") (pintype "passive"))
      (node (ref "U201") (pin "30") (pinfunction "PEXCREQ#_30") (pintype "output"))
    )
    (net (code "21") (name "/PCIe_RX_N") (class "Default")
      (node (ref "C228") (pin "2") (pinfunction "2_2") (pintype "passive"))
    )
    (net (code "22") (name "/PCIe_RX_P") (class "Default")
      (node (ref "C227") (pin "2") (pinfunction "2_2") (pintype "passive"))
    )
    (net (code "23") (name "/PCIe_TX_N") (class "Default")
      (node (ref "U201") (pin "28") (pinfunction "PEXRX-_28") (pintype "input"))
    )
    (net (code "24") (name "/PCIe_TX_P") (class "Default")
      (node (ref "U201") (pin "27") (pinfunction "PEXRX+_27") (pintype "input"))
    )
    (net (code "25") (name "/PCIe_nRST") (class "Default")
      (node (ref "C224") (pin "1") (pinfunction "1_1") (pintype "passive"))
      (node (ref "U201") (pin "19") (pinfunction "PEXRST#_19") (pintype "input"))
    )
    (net (code "26") (name "/PEXTX_N") (class "Default")
      (node (ref "C228") (pin "1") (pinfunction "1_1") (pintype "passive"))
      (node (ref "U201") (pin "25") (pinfunction "PEXTX-_25") (pintype "output"))
    )
    (net (code "27") (name "/PEXTX_P") (class "Default")
      (node (ref "C227") (pin "1") (pinfunction "1_1") (pintype "passive"))
      (node (ref "U201") (pin "24") (pinfunction "PEXTX+_24") (pintype "output"))
    )
    (net (code "28") (name "/PI-RX_STN-TX") (class "Default")
      (node (ref "J202") (pin "17") (pintype "input"))
    )
    (net (code "29") (name "/PI-TX_STN-RX") (class "Default")
      (node (ref "J202") (pin "15") (pintype "input"))
    )
    (net (code "30") (name "/PONRST") (class "Default")
      (node (ref "JP200") (pin "1") (pinfunction "1_1") (pintype "passive"))
      (node (ref "U201") (pin "31") (pinfunction "PONRST#_31") (pintype "input"))
    )
    (net (code "31") (name "/RESET_LTE_MODUL") (class "Default")
      (node (ref "J202") (pin "31") (pintype "input"))
    )
    (net (code "32") (name "/RESET_STN") (class "Default") (node (ref "J202") (pin "39") (pintype "input")))
    (net (code "33") (name "/RPI_RUNNING") (class "Default") (node (ref "J202") (pin "46") (pintype "input")))
    (net (code "34") (name "/SCK_CAN") (class "Default") (node (ref "J202") (pin "2") (pintype "input")))
    (net (code "35") (name "/SLEEP_STN") (class "Default") (node (ref "J202") (pin "37") (pintype "input")))
    (net (code "36") (name "/SSRX1_N") (class "Default")
      (node (ref "J200") (pin "14") (pinfunction "StdA_SSRX-_14") (pintype "output"))
      (node (ref "U201") (pin "56") (pinfunction "SSRX1-_56") (pintype "input"))
    )
    (net (code "37") (name "/SSRX1_P") (class "Default")
      (node (ref "J200") (pin "15") (pinfunction "StdA_SSRX+_15") (pintype "output"))
      (node (ref "U201") (pin "55") (pinfunction "SSRX1+_55") (pintype "input"))
    )
    (net (code "38") (name "/SSRX2_N") (class "Default")
      (node (ref "J200") (pin "5") (pinfunction "StdA_SSRX-_5") (pintype "output"))
      (node (ref "U201") (pin "65") (pinfunction "SSRX2-_65") (pintype "input"))
    )
    (net (code "39") (name "/SSRX2_P") (class "Default")
      (node (ref "J200") (pin "6") (pinfunction "StdA_SSRX+_6") (pintype "output"))
      (node (ref "U201") (pin "64") (pinfunction "SSRX2+_64") (pintype "input"))
    )
    (net (code "40") (name "/SSTX1_HUB_N") (class "Default")
      (node (ref "C223") (pin "2") (pinfunction "2_2") (pintype "passive"))
      (node (ref "U201") (pin "53") (pinfunction "SSTX1-_53") (pintype "output"))
    )
    (net (code "41") (name "/SSTX1_HUB_P") (class "Default")
      (node (ref "C222") (pin "2") (pinfunction "2_2") (pintype "passive"))
      (node (ref "U201") (pin "52") (pinfunction "SSTX1+_52") (pintype "output"))
    )
    (net (code "42") (name "/SSTX1_N") (class "Default")
      (node (ref "C223") (pin "1") (pinfunction "1_1") (pintype "passive"))
      (node (ref "J200") (pin "17") (pinfunction "StdA_SSTX-_17") (pintype "input"))
    )
    (net (code "43") (name "/SSTX1_P") (class "Default")
      (node (ref "C222") (pin "1") (pinfunction "1_1") (pintype "passive"))
      (node (ref "J200") (pin "18") (pinfunction "StdA_SSTX+_18") (pintype "input"))
    )
    (net (code "44") (name "/SSTX2_HUB_N") (class "Default")
      (node (ref "C226") (pin "2") (pinfunction "2_2") (pintype "passive"))
      (node (ref "U201") (pin "62") (pinfunction "SSTX2-_62") (pintype "output"))
    )
    (net (code "45") (name "/SSTX2_HUB_P") (class "Default")
      (node (ref "C225") (pin "2") (pinfunction "2_2") (pintype "passive"))
      (node (ref "U201") (pin "61") (pinfunction "SSTX2+_61") (pintype "output"))
    )
    (net (code "46") (name "/SSTX2_N") (class "Default")
      (node (ref "C226") (pin "1") (pinfunction "1_1") (pintype "passive"))
      (node (ref "J200") (pin "8") (pinfunction "StdA_SSTX-_8") (pintype "input"))
    )
    (net (code "47") (name "/SSTX2_P") (class "Default")
      (node (ref "C225") (pin "1") (pinfunction "1_1") (pintype "passive"))
      (node (ref "J200") (pin "9") (pinfunction "StdA_SSTX+_9") (pintype "input"))
    )
    (net (code "48") (name "/SSXI") (class "Default")
      (node (ref "R208") (pin "1") (pinfunction "1_1") (pintype "passive"))
      (node (ref "U201") (pin "47") (pinfunction "SSXI_47") (pintype "input"))
    )
    (net (code "49") (name "/SSXO") (class "Default")
      (node (ref "C229") (pin "2") (pinfunction "2_2") (pintype "passive"))
      (node (ref "U201") (pin "48") (pinfunction "SSXO_48") (pintype "output"))
      (node (ref "Y200") (pin "1") (pinfunction "1_1") (pintype "passive"))
    )
    (net (code "50") (name "/STN_RUNNING") (class "Default") (node (ref "J202") (pin "50") (pintype "input")))
    (net (code "51") (name "/SW") (class "Default")
      (node (ref "D200") (pin "1") (pinfunction "C_1") (pintype "passive"))
      (node (ref "L200") (pin "1") (pinfunction "1_1") (pintype "passive"))
      (node (ref "U200") (pin "1") (pinfunction "SW_1") (pintype "power_in"))
    )
    (net (code "52") (name "/TURN_OFF_GNSS") (class "Default")
      (node (ref "J202") (pin "21") (pintype "input"))
    )
    (net (code "53") (name "/TURN_OFF_WWAN") (class "Default")
      (node (ref "J202") (pin "25") (pintype "input"))
    )
    (net (code "54") (name "/USB2D1_N") (class "Default")
      (node (ref "J200") (pin "11") (pinfunction "D-_11") (pintype "bidirectional"))
      (node (ref "U201") (pin "59") (pinfunction "USB2D1-_59") (pintype "bidirectional"))
    )
    (net (code "55") (name "/USB2D1_P") (class "Default")
      (node (ref "J200") (pin "12") (pinfunction "D+_12") (pintype "bidirectional"))
      (node (ref "U201") (pin "58") (pinfunction "USB2D1+_58") (pintype "bidirectional"))
    )
    (net (code "56") (name "/USB2D2_N") (class "Default")
      (node (ref "J200") (pin "2") (pinfunction "D-_2") (pintype "bidirectional"))
      (node (ref "U201") (pin "68") (pinfunction "USB2D2-_68") (pintype "bidirectional"))
    )
    (net (code "57") (name "/USB2D2_P") (class "Default")
      (node (ref "J200") (pin "3") (pinfunction "D+_3") (pintype "bidirectional"))
      (node (ref "U201") (pin "67") (pinfunction "USB2D2+_67") (pintype "bidirectional"))
    )
    (net (code "58") (name "/USB2D3_N") (class "Default")
      (node (ref "J201") (pin "2") (pinfunction "D-_2") (pintype "bidirectional"))
      (node (ref "U201") (pin "8") (pinfunction "USB2D3-_8") (pintype "bidirectional"))
    )
    (net (code "59") (name "/USB2D3_P") (class "Default")
      (node (ref "J201") (pin "3") (pinfunction "D+_3") (pintype "bidirectional"))
      (node (ref "U201") (pin "7") (pinfunction "USB2D3+_7") (pintype "bidirectional"))
    )
    (net (code "60") (name "/USB2D4_N") (class "Default")
      (node (ref "J201") (pin "6") (pinfunction "D-_6") (pintype "bidirectional"))
      (node (ref "U201") (pin "17") (pinfunction "USB2D4-_17") (pintype "bidirectional"))
    )
    (net (code "61") (name "/USB2D4_P") (class "Default")
      (node (ref "J201") (pin "7") (pinfunction "D+_7") (pintype "bidirectional"))
      (node (ref "U201") (pin "16") (pinfunction "USB2D4+_16") (pintype "bidirectional"))
    )
    (net (code "62") (name "/USB_OTG") (class "Default") (node (ref "J202") (pin "1") (pintype "input")))
    (net (code "63") (name "/USB_UP_N") (class "Default") (node (ref "J202") (pin "7") (pintype "input")))
    (net (code "64") (name "/USB_UP_P") (class "Default") (node (ref "J202") (pin "5") (pintype "input")))
    (net (code "65") (name "/VBUS1") (class "Default")
      (node (ref "J200") (pin "10") (pinfunction "VBUS_10") (pintype "power_in"))
      (node (ref "U202") (pin "6") (pinfunction "OUT2_6") (pintype "power_in"))
    )
    (net (code "66") (name "/VBUS2") (class "Default")
      (node (ref "J200") (pin "1") (pinfunction "VBUS_1") (pintype "power_in"))
      (node (ref "U202") (pin "7") (pinfunction "OUT1_7") (pintype "power_in"))
    )
    (net (code "67") (name "/VBUS3") (class "Default")
      (node (ref "J201") (pin "1") (pinfunction "VBUS_1") (pintype "power_in"))
      (node (ref "U203") (pin "6") (pinfunction "OUT2_6") (pintype "power_in"))
    )
    (net (code "68") (name "/VBUS4") (class "Default")
      (node (ref "J201") (pin "5") (pinfunction "VBUS_5") (pintype "power_in"))
      (node (ref "U203") (pin "7") (pinfunction "OUT1_7") (pintype "power_in"))
    )
    (net (code "69") (name "/nCS1_CAN") (class "Default") (node (ref "J202") (pin "12") (pintype "input")))
    (net (code "70") (name "/nCS2_CAN") (class "Default") (node (ref "J202") (pin "22") (pintype "input")))
    (net (code "71") (name "/nINT1_CAN") (class "Default") (node (ref "J202") (pin "16") (pintype "input")))
    (net (code "72") (name "/nINT2_CAN") (class "Default") (node (ref "J202") (pin "20") (pintype "input")))
    (net (code "73") (name "/nRES_USB") (class "Default")
      (node (ref "JP200") (pin "2") (pinfunction "2_2") (pintype "passive"))
    )
    (net (code "74") (name "1V05") (class "Default")
      (node (ref "C211") (pin "1") (pinfunction "1_1") (pintype "passive"))
      (node (ref "C212") (pin "1") (pinfunction "1_1") (pintype "passive"))
      (node (ref "C213") (pin "1") (pinfunction "1_1") (pintype "passive"))
      (node (ref "C214") (pin "1") (pinfunction "1_1") (pintype "passive"))
      (node (ref "C215") (pin "1") (pinfunction "1_1") (pintype "passive"))
      (node (ref "C216") (pin "1") (pinfunction "1_1") (pintype "passive"))
      (node (ref "C217") (pin "1") (pinfunction "1_1") (pintype "passive"))
      (node (ref "C218") (pin "1") (pinfunction "1_1") (pintype "passive"))
      (node (ref "C219") (pin "1") (pinfunction "1_1") (pintype "passive"))
      (node (ref "C220") (pin "1") (pinfunction "1_1") (pintype "passive"))
      (node (ref "C221") (pin "1") (pinfunction "1_1") (pintype "passive"))
      (node (ref "C233") (pin "1") (pinfunction "1_1") (pintype "passive"))
      (node (ref "C237") (pin "1") (pinfunction "1_1") (pintype "passive"))
      (node (ref "L200") (pin "2") (pinfunction "2_2") (pintype "passive"))
      (node (ref "R200") (pin "1") (pinfunction "1_1") (pintype "passive"))
      (node (ref "U201") (pin "12") (pinfunction "VCCA10SSRX34_12") (pintype "power_in"))
      (node (ref "U201") (pin "29") (pinfunction "VDD_29") (pintype "power_in"))
      (node (ref "U201") (pin "3") (pinfunction "VCCA10SSRX34_3") (pintype "power_in"))
      (node (ref "U201") (pin "45") (pinfunction "VDD_45") (pintype "power_in"))
      (node (ref "U201") (pin "54") (pinfunction "VCCA10SSRX12_54") (pintype "power_in"))
      (node (ref "U201") (pin "60") (pinfunction "VDD_60") (pintype "power_in"))
      (node (ref "U201") (pin "63") (pinfunction "VCCA10SSRX12_63") (pintype "power_in"))
      (node (ref "U201") (pin "9") (pinfunction "VDD_9") (pintype "power_in"))
    )
    (net (code "75") (name "3V3") (class "Default")
      (node (ref "C200") (pin "1") (pinfunction "1_1") (pintype "passive"))
      (node (ref "C201") (pin "1") (pinfunction "1_1") (pintype "passive"))
      (node (ref "C202") (pin "1") (pinfunction "1_1") (pintype "passive"))
      (node (ref "C203") (pin "1") (pinfunction "1_1") (pintype "passive"))
      (node (ref "C204") (pin "1") (pinfunction "1_1") (pintype "passive"))
      (node (ref "C205") (pin "1") (pinfunction "1_1") (pintype "passive"))
      (node (ref "C206") (pin "1") (pinfunction "1_1") (pintype "passive"))
      (node (ref "C207") (pin "1") (pinfunction "1_1") (pintype "passive"))
      (node (ref "C208") (pin "1") (pinfunction "1_1") (pintype "passive"))
      (node (ref "D201") (pin "1") (pinfunction "C_1") (pintype "passive"))
      (node (ref "J202") (pin "41") (pintype "input"))
      (node (ref "J202") (pin "43") (pintype "input"))
      (node (ref "R203") (pin "2") (pinfunction "2_2") (pintype "passive"))
      (node (ref "R204") (pin "1") (pinfunction "1_1") (pintype "passive"))
      (node (ref "R205") (pin "1") (pinfunction "1_1") (pintype "passive"))
      (node (ref "R207") (pin "1") (pinfunction "1_1") (pintype "passive"))
      (node (ref "R209") (pin "1") (pinfunction "1_1") (pintype "passive"))
      (node (ref "R210") (pin "1") (pinfunction "1_1") (pintype "passive"))
      (node (ref "R211") (pin "1") (pinfunction "1_1") (pintype "passive"))
      (node (ref "R212") (pin "1") (pinfunction "1_1") (pintype "passive"))
      (node (ref "R213") (pin "1") (pinfunction "1_1") (pintype "passive"))
      (node (ref "R214") (pin "1") (pinfunction "1_1") (pintype "passive"))
      (node (ref "R215") (pin "1") (pinfunction "1_1") (pintype "passive"))
      (node (ref "R216") (pin "1") (pinfunction "1_1") (pintype "passive"))
      (node (ref "U201") (pin "15") (pinfunction "VCCA33SS34_15") (pintype "power_in"))
      (node (ref "U201") (pin "23") (pinfunction "VCCA33PEX_23") (pintype "power_in"))
      (node (ref "U201") (pin "32") (pinfunction "VSUS33_32") (pintype "power_in"))
      (node (ref "U201") (pin "46") (pinfunction "VSUS33_46") (pintype "power_in"))
      (node (ref "U201") (pin "49") (pinfunction "VCCA33SSM_49") (pintype "power_in"))
      (node (ref "U201") (pin "57") (pinfunction "VCCA33SS12_57") (pintype "power_in"))
      (node (ref "U201") (pin "6") (pinfunction "VCCA33SS34_6") (pintype "power_in"))
      (node (ref "U201") (pin "66") (pinfunction "VCCA33SS12_66") (pintype "power_in"))
    )
    (net (code "76") (name "3V3_PO") (class "Default") (node (ref "J202") (pin "28") (pintype "input")))
    (net (code "77") (name "5V") (class "Default")
      (node (ref "C209") (pin "1") (pinfunction "1_1") (pintype "passive"))
      (node (ref "C210") (pin "1") (pinfunction "1_1") (pintype "passive"))
      (node (ref "C231") (pin "1") (pinfunction "1_1") (pintype "passive"))
      (node (ref "C232") (pin "1") (pinfunction "1_1") (pintype "passive"))
      (node (ref "C234") (pin "2") (pinfunction "2_2") (pintype "passive"))
      (node (ref "C235") (pin "1") (pinfunction "1_1") (pintype "passive"))
      (node (ref "C236") (pin "1") (pinfunction "1_1") (pintype "passive"))
      (node (ref "C239") (pin "1") (pinfunction "1_1") (pintype "passive"))
      (node (ref "C240") (pin "1") (pinfunction "1_1") (pintype "passive"))
      (node (ref "J202") (pin "11") (pintype "input"))
      (node (ref "J202") (pin "47") (pintype "input"))
      (node (ref "J202") (pin "49") (pintype "input"))
      (node (ref "J202") (pin "9") (pintype "input"))
      (node (ref "R201") (pin "2") (pinfunction "2_2") (pintype "passive"))
      (node (ref "U200") (pin "5") (pinfunction "VIN_5") (pintype "power_in"))
      (node (ref "U202") (pin "2") (pinfunction "IN_2") (pintype "power_in"))
      (node (ref "U203") (pin "2") (pinfunction "IN_2") (pintype "power_in"))
    )
    (net (code "78") (name "5V_PO") (class "Default")
      (node (ref "J202") (pin "36") (pintype "input"))
      (node (ref "J202") (pin "38") (pintype "input"))
    )
    (net (code "79") (name "GND") (class "Default")
      (node (ref "C200") (pin "2") (pinfunction "2_2") (pintype "passive"))
      (node (ref "C201") (pin "2") (pinfunction "2_2") (pintype "passive"))
      (node (ref "C202") (pin "2") (pinfunction "2_2") (pintype "passive"))
      (node (ref "C203") (pin "2") (pinfunction "2_2") (pintype "passive"))
      (node (ref "C204") (pin "2") (pinfunction "2_2") (pintype "passive"))
      (node (ref "C205") (pin "2") (pinfunction "2_2") (pintype "passive"))
      (node (ref "C206") (pin "2") (pinfunction "2_2") (pintype "passive"))
      (node (ref "C207") (pin "2") (pinfunction "2_2") (pintype "passive"))
      (node (ref "C208") (pin "2") (pinfunction "2_2") (pintype "passive"))
      (node (ref "C209") (pin "2") (pinfunction "2_2") (pintype "passive"))
      (node (ref "C210") (pin "2") (pinfunction "2_2") (pintype "passive"))
      (node (ref "C211") (pin "2") (pinfunction "2_2") (pintype "passive"))
      (node (ref "C212") (pin "2") (pinfunction "2_2") (pintype "passive"))
      (node (ref "C213") (pin "2") (pinfunction "2_2") (pintype "passive"))
      (node (ref "C214") (pin "2") (pinfunction "2_2") (pintype "passive"))
      (node (ref "C215") (pin "2") (pinfunction "2_2") (pintype "passive"))
      (node (ref "C216") (pin "2") (pinfunction "2_2") (pintype "passive"))
      (node (ref "C217") (pin "2") (pinfunction "2_2") (pintype "passive"))
      (node (ref "C218") (pin "2") (pinfunction "2_2") (pintype "passive"))
      (node (ref "C219") (pin "2") (pinfunction "2_2") (pintype "passive"))
      (node (ref "C220") (pin "2") (pinfunction "2_2") (pintype "passive"))
      (node (ref "C221") (pin "2") (pinfunction "2_2") (pintype "passive"))
      (node (ref "C224") (pin "2") (pinfunction "2_2") (pintype "passive"))
      (node (ref "C229") (pin "1") (pinfunction "1_1") (pintype "passive"))
      (node (ref "C230") (pin "1") (pinfunction "1_1") (pintype "passive"))
      (node (ref "C231") (pin "2") (pinfunction "2_2") (pintype "passive"))
      (node (ref "C232") (pin "2") (pinfunction "2_2") (pintype "passive"))
      (node (ref "C233") (pin "2") (pinfunction "2_2") (pintype "passive"))
      (node (ref "C234") (pin "1") (pinfunction "1_1") (pintype "passive"))
      (node (ref "C235") (pin "2") (pinfunction "2_2") (pintype "passive"))
      (node (ref "C236") (pin "2") (pinfunction "2_2") (pintype "passive"))
      (node (ref "C237") (pin "2") (pinfunction "2_2") (pintype "passive"))
      (node (ref "C238") (pin "2") (pinfunction "2_2") (pintype "passive"))
      (node (ref "C239") (pin "2") (pinfunction "2_2") (pintype "passive"))
      (node (ref "C240") (pin "2") (pinfunction "2_2") (pintype "passive"))
      (node (ref "D200") (pin "2") (pinfunction "A_2") (pintype "passive"))
      (node (ref "J200") (pin "13") (pinfunction "GND_13") (pintype "power_in"))
      (node (ref "J200") (pin "16") (pinfunction "GND_DRAIN_16") (pintype "power_in"))
      (node (ref "J200") (pin "19") (pinfunction "Shield_19") (pintype "passive"))
      (node (ref "J200") (pin "4") (pinfunction "GND_4") (pintype "power_in"))
      (node (ref "J200") (pin "7") (pinfunction "GND_DRAIN_7") (pintype "power_in"))
      (node (ref "J201") (pin "4") (pinfunction "GND_4") (pintype "power_in"))
      (node (ref "J201") (pin "8") (pinfunction "GND_8") (pintype "power_in"))
      (node (ref "J201") (pin "9") (pinfunction "Shield_9") (pintype "passive"))
      (node (ref "J202") (pin "10") (pintype "input"))
      (node (ref "J202") (pin "13") (pintype "input"))
      (node (ref "J202") (pin "14") (pintype "input"))
      (node (ref "J202") (pin "18") (pintype "input"))
      (node (ref "J202") (pin "19") (pintype "input"))
      (node (ref "J202") (pin "23") (pintype "input"))
      (node (ref "J202") (pin "26") (pintype "input"))
      (node (ref "J202") (pin "29") (pintype "input"))
      (node (ref "J202") (pin "3") (pintype "input"))
      (node (ref "J202") (pin "34") (pintype "input"))
      (node (ref "J202") (pin "35") (pintype "input"))
      (node (ref "J202") (pin "40") (pintype "input"))
      (node (ref "J202") (pin "44") (pintype "input"))
      (node (ref "J202") (pin "45") (pintype "input"))
      (node (ref "J202") (pin "48") (pintype "input"))
      (node (ref "J202") (pin "6") (pintype "input"))
      (node (ref "R202") (pin "1") (pinfunction "1_1") (pintype "passive"))
      (node (ref "R206") (pin "1") (pinfunction "1_1") (pintype "passive"))
      (node (ref "U200") (pin "2") (pinfunction "GND_2") (pintype "power_in"))
      (node (ref "U201") (pin "69") (pinfunction "EP_69") (pintype "power_in"))
      (node (ref "U202") (pin "1") (pinfunction "GND_1") (pintype "power_in"))
      (node (ref "U202") (pin "9") (pinfunction "ePad_9") (pintype "power_in"))
      (node (ref "U203") (pin "1") (pinfunction "GND_1") (pintype "power_in"))
      (node (ref "U203") (pin "9") (pinfunction "ePad_9") (pintype "power_in"))
      (node (ref "Y200") (pin "2") (pinfunction "GND_2") (pintype "power_in"))
      (node (ref "Y200") (pin "4") (pinfunction "GND_4") (pintype "power_in"))
    )
    (net (code "80") (name "Net-(C230-Pad2)") (class "Default")
      (node (ref "C230") (pin "2") (pinfunction "2_2") (pintype "passive"))
      (node (ref "R208") (pin "2") (pinfunction "2_2") (pintype "passive"))
      (node (ref "Y200") (pin "3") (pinfunction "3_3") (pintype "passive"))
    )
    (net (code "81") (name "Net-(D201-A)") (class "Default")
      (node (ref "C238") (pin "1") (pinfunction "1_1") (pintype "passive"))
      (node (ref "D201") (pin "2") (pinfunction "A_2") (pintype "passive"))
      (node (ref "JP200") (pin "3") (pinfunction "3_3") (pintype "passive"))
      (node (ref "R203") (pin "1") (pinfunction "1_1") (pintype "passive"))
    )
    (net (code "82") (name "Net-(U200-EN)") (class "Default")
      (node (ref "R201") (pin "1") (pinfunction "1_1") (pintype "passive"))
      (node (ref "U200") (pin "4") (pinfunction "EN_4") (pintype "input"))
    )
    (net (code "83") (name "Net-(U201-PEXWAKE#)") (class "Default")
      (node (ref "R204") (pin "2") (pinfunction "2_2") (pintype "passive"))
      (node (ref "U201") (pin "20") (pinfunction "PEXWAKE#_20") (pintype "output"))
    )
    (net (code "84") (name "Net-(U201-SMI#)") (class "Default")
      (node (ref "R207") (pin "2") (pinfunction "2_2") (pintype "passive"))
      (node (ref "U201") (pin "18") (pinfunction "SMI#_18") (pintype "output"))
    )
    (net (code "85") (name "Net-(U201-SSREXT)") (class "Default")
      (node (ref "R206") (pin "2") (pinfunction "2_2") (pintype "passive"))
      (node (ref "U201") (pin "50") (pinfunction "SSREXT_50") (pintype "passive"))
    )
    (net (code "86") (name "unconnected-(MP200-PE-Pad1)") (class "Default")
      (node (ref "MP200") (pin "1") (pinfunction "PE_1") (pintype "passive"))
    )
    (net (code "87") (name "unconnected-(MP201-PE-Pad1)") (class "Default")
      (node (ref "MP201") (pin "1") (pinfunction "PE_1") (pintype "passive"))
    )
    (net (code "88") (name "unconnected-(MP202-PE-Pad1)") (class "Default")
      (node (ref "MP202") (pin "1") (pinfunction "PE_1") (pintype "passive"))
    )
    (net (code "89") (name "unconnected-(MP203-PE-Pad1)") (class "Default")
      (node (ref "MP203") (pin "1") (pinfunction "PE_1") (pintype "passive"))
    )
    (net (code "90") (name "unconnected-(U201-NC-Pad26)") (class "Default")
      (node (ref "U201") (pin "26") (pinfunction "NC_26") (pintype "passive"))
    )
    (net (code "91") (name "unconnected-(U201-SPICK-Pad35)") (class "Default")
      (node (ref "U201") (pin "35") (pinfunction "SPICK_35") (pintype "output+no_connect"))
    )
    (net (code "92") (name "unconnected-(U201-SPICS#-Pad34)") (class "Default")
      (node (ref "U201") (pin "34") (pinfunction "SPICS#_34") (pintype "output+no_connect"))
    )
    (net (code "93") (name "unconnected-(U201-SPISI-Pad36)") (class "Default")
      (node (ref "U201") (pin "36") (pinfunction "SPISI_36") (pintype "output+no_connect"))
    )
    (net (code "94") (name "unconnected-(U201-SPISO-Pad33)") (class "Default")
      (node (ref "U201") (pin "33") (pinfunction "SPISO_33") (pintype "input+no_connect"))
    )
    (net (code "95") (name "unconnected-(U201-SSRX3+-Pad4)") (class "Default")
      (node (ref "U201") (pin "4") (pinfunction "SSRX3+_4") (pintype "input+no_connect"))
    )
    (net (code "96") (name "unconnected-(U201-SSRX3--Pad5)") (class "Default")
      (node (ref "U201") (pin "5") (pinfunction "SSRX3-_5") (pintype "input+no_connect"))
    )
    (net (code "97") (name "unconnected-(U201-SSRX4+-Pad13)") (class "Default")
      (node (ref "U201") (pin "13") (pinfunction "SSRX4+_13") (pintype "input+no_connect"))
    )
    (net (code "98") (name "unconnected-(U201-SSRX4--Pad14)") (class "Default")
      (node (ref "U201") (pin "14") (pinfunction "SSRX4-_14") (pintype "input+no_connect"))
    )
    (net (code "99") (name "unconnected-(U201-SSTX3+-Pad1)") (class "Default")
      (node (ref "U201") (pin "1") (pinfunction "SSTX3+_1") (pintype "output+no_connect"))
    )
    (net (code "100") (name "unconnected-(U201-SSTX3--Pad2)") (class "Default")
      (node (ref "U201") (pin "2") (pinfunction "SSTX3-_2") (pintype "output+no_connect"))
    )
    (net (code "101") (name "unconnected-(U201-SSTX4+-Pad10)") (class "Default")
      (node (ref "U201") (pin "10") (pinfunction "SSTX4+_10") (pintype "output+no_connect"))
    )
    (net (code "102") (name "unconnected-(U201-SSTX4--Pad11)") (class "Default")
      (node (ref "U201") (pin "11") (pinfunction "SSTX4-_11") (pintype "output+no_connect"))
    )
    (net (code "103") (name "unconnected-(U201-TESTEN-Pad51)") (class "Default")
      (node (ref "U201") (pin "51") (pinfunction "TESTEN_51") (pintype "input+no_connect"))
    )
  )
)
